# Concentrator_and_Modem_Headers.net
KiCad netlist of a schematic drawn in Altium Designer
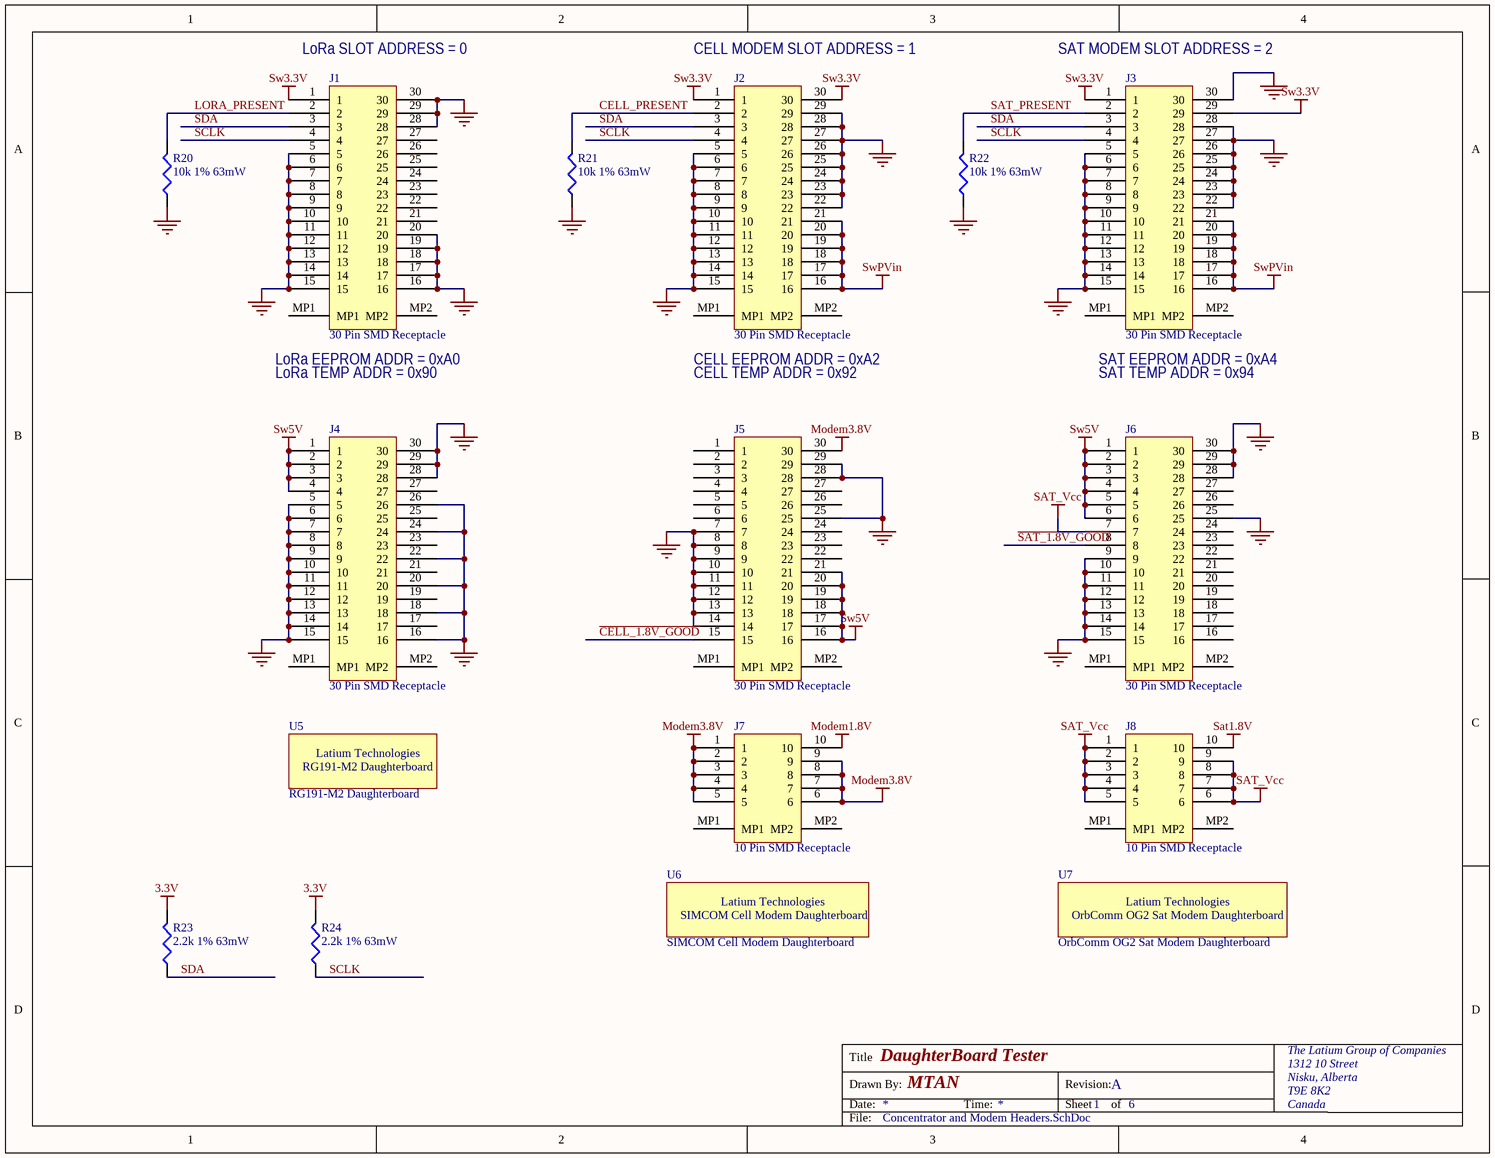
[diagram p0: Concentrator and Modem Headers.SchDoc]

(export (version "E")
  (design (tool "Eeschema 10.0.6"))
  (components
    (comp (ref "J1")
      (value "30 Pin SMD Receptacle")
      (footprint "10132798-031100LF")
      (description "CONN RCPT 30POS SMD GOLD")
      (fields
        (field (name "MANUFACTURER") "Amphenol ICC (FCI)")
        (field (name "MANUFACTURER PART NUMBER") "10132798-031100LF")
      )
      (libsource (lib "Latium Component Library") (part "Amphenol 30 Pos BergStak Plug"))
    )
    (comp (ref "J2")
      (value "30 Pin SMD Receptacle")
      (footprint "10132798-031100LF")
      (description "CONN RCPT 30POS SMD GOLD")
      (fields
        (field (name "MANUFACTURER") "Amphenol ICC (FCI)")
        (field (name "MANUFACTURER PART NUMBER") "10132798-031100LF")
      )
      (libsource (lib "Latium Component Library") (part "Amphenol 30 Pos BergStak Plug"))
    )
    (comp (ref "J3")
      (value "30 Pin SMD Receptacle")
      (footprint "10132798-031100LF")
      (description "CONN RCPT 30POS SMD GOLD")
      (fields
        (field (name "MANUFACTURER") "Amphenol ICC (FCI)")
        (field (name "MANUFACTURER PART NUMBER") "10132798-031100LF")
      )
      (libsource (lib "Latium Component Library") (part "Amphenol 30 Pos BergStak Plug"))
    )
    (comp (ref "J4")
      (value "30 Pin SMD Receptacle")
      (footprint "10132798-031100LF")
      (description "CONN RCPT 30POS SMD GOLD")
      (fields
        (field (name "MANUFACTURER") "Amphenol ICC (FCI)")
        (field (name "MANUFACTURER PART NUMBER") "10132798-031100LF")
      )
      (libsource (lib "Latium Component Library") (part "Amphenol 30 Pos BergStak Plug"))
    )
    (comp (ref "J5")
      (value "30 Pin SMD Receptacle")
      (footprint "10132798-031100LF")
      (description "CONN RCPT 30POS SMD GOLD")
      (fields
        (field (name "MANUFACTURER") "Amphenol ICC (FCI)")
        (field (name "MANUFACTURER PART NUMBER") "10132798-031100LF")
      )
      (libsource (lib "Latium Component Library") (part "Amphenol 30 Pos BergStak Plug"))
    )
    (comp (ref "J6")
      (value "30 Pin SMD Receptacle")
      (footprint "10132798-031100LF")
      (description "CONN RCPT 30POS SMD GOLD")
      (fields
        (field (name "MANUFACTURER") "Amphenol ICC (FCI)")
        (field (name "MANUFACTURER PART NUMBER") "10132798-031100LF")
      )
      (libsource (lib "Latium Component Library") (part "Amphenol 30 Pos BergStak Plug"))
    )
    (comp (ref "J7")
      (value "10 Pin SMD Receptacle")
      (footprint "10132798-011100LF")
      (description "CONN RCPT 10POS SMD GOLD")
      (fields
        (field (name "MANUFACTURER") "Amphenol ICC (FCI)")
        (field (name "MANUFACTURER PART NUMBER") "10132798-011100LF")
      )
      (libsource (lib "Latium Component Library") (part "Amphenol 10 Pos BergStak Plug"))
    )
    (comp (ref "J8")
      (value "10 Pin SMD Receptacle")
      (footprint "10132798-011100LF")
      (description "CONN RCPT 10POS SMD GOLD")
      (fields
        (field (name "MANUFACTURER") "Amphenol ICC (FCI)")
        (field (name "MANUFACTURER PART NUMBER") "10132798-011100LF")
      )
      (libsource (lib "Latium Component Library") (part "Amphenol 10 Pos BergStak Plug"))
    )
    (comp (ref "R20")
      (value "10k 1% 63mW")
      (footprint "RESC1005L")
      (description "Resistor")
      (libsource (lib "Miscellaneous Devices") (part "Res3"))
    )
    (comp (ref "R21")
      (value "10k 1% 63mW")
      (footprint "RESC1005L")
      (description "Resistor")
      (libsource (lib "Miscellaneous Devices") (part "Res3"))
    )
    (comp (ref "R22")
      (value "10k 1% 63mW")
      (footprint "RESC1005L")
      (description "Resistor")
      (libsource (lib "Miscellaneous Devices") (part "Res3"))
    )
    (comp (ref "R23")
      (value "2.2k 1% 63mW")
      (footprint "RESC1005L")
      (description "Resistor")
      (libsource (lib "Miscellaneous Devices") (part "Res3"))
    )
    (comp (ref "R24")
      (value "2.2k 1% 63mW")
      (footprint "RESC1005L")
      (description "Resistor")
      (libsource (lib "Miscellaneous Devices") (part "Res3"))
    )
    (comp (ref "U5")
      (value "RG191-M2 Daughterboard")
      (footprint "RG191-M2 LoRa Daughterboard")
      (libsource (lib "Latium Component Library") (part "RG191-M2 Daughterboard"))
    )
    (comp (ref "U6")
      (value "SIMCOM Cell Modem Daughterboard")
      (footprint "SIMCOM Cell Modem Daughterboard")
      (libsource (lib "Latium Component Library") (part "SIMCOM Cell Modem Daughterboard"))
    )
    (comp (ref "U7")
      (value "OrbComm OG2 Sat Modem Daughterboard")
      (footprint "OrbComm OG2 Daughterboard")
      (libsource (lib "Latium Component Library") (part "OrbComm OG2 Sat Modem Daughterboard"))
    )
  )
  (nets
    (net (code "1") (name "/CELL_PRESENT") (class "Default")
      (node (ref "J2") (pin "2") (pinfunction "2_2") (pintype "passive"))
      (node (ref "R21") (pin "2") (pinfunction "2_2") (pintype "passive"))
    )
    (net (code "2") (name "/LORA_PRESENT") (class "Default")
      (node (ref "J1") (pin "2") (pinfunction "2_2") (pintype "passive"))
      (node (ref "R20") (pin "2") (pinfunction "2_2") (pintype "passive"))
    )
    (net (code "3") (name "/SAT_PRESENT") (class "Default")
      (node (ref "J3") (pin "2") (pinfunction "2_2") (pintype "passive"))
      (node (ref "R22") (pin "2") (pinfunction "2_2") (pintype "passive"))
    )
    (net (code "4") (name "/SCLK") (class "Default")
      (node (ref "J1") (pin "4") (pinfunction "4_4") (pintype "passive"))
      (node (ref "J2") (pin "4") (pinfunction "4_4") (pintype "passive"))
      (node (ref "J3") (pin "4") (pinfunction "4_4") (pintype "passive"))
      (node (ref "R24") (pin "1") (pinfunction "1_1") (pintype "passive"))
    )
    (net (code "5") (name "/SDA") (class "Default")
      (node (ref "J1") (pin "3") (pinfunction "3_3") (pintype "passive"))
      (node (ref "J2") (pin "3") (pinfunction "3_3") (pintype "passive"))
      (node (ref "J3") (pin "3") (pinfunction "3_3") (pintype "passive"))
      (node (ref "R23") (pin "1") (pinfunction "1_1") (pintype "passive"))
    )
    (net (code "6") (name "/~{CELL_1.8V_GOOD}") (class "Default")
      (node (ref "J5") (pin "15") (pinfunction "15_15") (pintype "passive"))
    )
    (net (code "7") (name "/~{SAT_1.8V_GOOD}") (class "Default")
      (node (ref "J6") (pin "8") (pinfunction "8_8") (pintype "passive"))
    )
    (net (code "8") (name "3.3V") (class "Default")
      (node (ref "R23") (pin "2") (pinfunction "2_2") (pintype "passive"))
      (node (ref "R24") (pin "2") (pinfunction "2_2") (pintype "passive"))
    )
    (net (code "9") (name "GND") (class "Default")
      (node (ref "J1") (pin "10") (pinfunction "10_10") (pintype "passive"))
      (node (ref "J1") (pin "11") (pinfunction "11_11") (pintype "passive"))
      (node (ref "J1") (pin "12") (pinfunction "12_12") (pintype "passive"))
      (node (ref "J1") (pin "13") (pinfunction "13_13") (pintype "passive"))
      (node (ref "J1") (pin "14") (pinfunction "14_14") (pintype "passive"))
      (node (ref "J1") (pin "15") (pinfunction "15_15") (pintype "passive"))
      (node (ref "J1") (pin "16") (pinfunction "16_16") (pintype "passive"))
      (node (ref "J1") (pin "17") (pinfunction "17_17") (pintype "passive"))
      (node (ref "J1") (pin "18") (pinfunction "18_18") (pintype "passive"))
      (node (ref "J1") (pin "19") (pinfunction "19_19") (pintype "passive"))
      (node (ref "J1") (pin "20") (pinfunction "20_20") (pintype "passive"))
      (node (ref "J1") (pin "28") (pinfunction "28_28") (pintype "passive"))
      (node (ref "J1") (pin "29") (pinfunction "29_29") (pintype "passive"))
      (node (ref "J1") (pin "30") (pinfunction "30_30") (pintype "passive"))
      (node (ref "J1") (pin "5") (pinfunction "5_5") (pintype "passive"))
      (node (ref "J1") (pin "6") (pinfunction "6_6") (pintype "passive"))
      (node (ref "J1") (pin "7") (pinfunction "7_7") (pintype "passive"))
      (node (ref "J1") (pin "8") (pinfunction "8_8") (pintype "passive"))
      (node (ref "J1") (pin "9") (pinfunction "9_9") (pintype "passive"))
      (node (ref "J2") (pin "10") (pinfunction "10_10") (pintype "passive"))
      (node (ref "J2") (pin "11") (pinfunction "11_11") (pintype "passive"))
      (node (ref "J2") (pin "12") (pinfunction "12_12") (pintype "passive"))
      (node (ref "J2") (pin "13") (pinfunction "13_13") (pintype "passive"))
      (node (ref "J2") (pin "14") (pinfunction "14_14") (pintype "passive"))
      (node (ref "J2") (pin "15") (pinfunction "15_15") (pintype "passive"))
      (node (ref "J2") (pin "22") (pinfunction "22_22") (pintype "passive"))
      (node (ref "J2") (pin "23") (pinfunction "23_23") (pintype "passive"))
      (node (ref "J2") (pin "24") (pinfunction "24_24") (pintype "passive"))
      (node (ref "J2") (pin "25") (pinfunction "25_25") (pintype "passive"))
      (node (ref "J2") (pin "26") (pinfunction "26_26") (pintype "passive"))
      (node (ref "J2") (pin "27") (pinfunction "27_27") (pintype "passive"))
      (node (ref "J2") (pin "28") (pinfunction "28_28") (pintype "passive"))
      (node (ref "J2") (pin "29") (pinfunction "29_29") (pintype "passive"))
      (node (ref "J2") (pin "5") (pinfunction "5_5") (pintype "passive"))
      (node (ref "J2") (pin "6") (pinfunction "6_6") (pintype "passive"))
      (node (ref "J2") (pin "7") (pinfunction "7_7") (pintype "passive"))
      (node (ref "J2") (pin "8") (pinfunction "8_8") (pintype "passive"))
      (node (ref "J2") (pin "9") (pinfunction "9_9") (pintype "passive"))
      (node (ref "J3") (pin "10") (pinfunction "10_10") (pintype "passive"))
      (node (ref "J3") (pin "11") (pinfunction "11_11") (pintype "passive"))
      (node (ref "J3") (pin "12") (pinfunction "12_12") (pintype "passive"))
      (node (ref "J3") (pin "13") (pinfunction "13_13") (pintype "passive"))
      (node (ref "J3") (pin "14") (pinfunction "14_14") (pintype "passive"))
      (node (ref "J3") (pin "15") (pinfunction "15_15") (pintype "passive"))
      (node (ref "J3") (pin "22") (pinfunction "22_22") (pintype "passive"))
      (node (ref "J3") (pin "23") (pinfunction "23_23") (pintype "passive"))
      (node (ref "J3") (pin "24") (pinfunction "24_24") (pintype "passive"))
      (node (ref "J3") (pin "25") (pinfunction "25_25") (pintype "passive"))
      (node (ref "J3") (pin "26") (pinfunction "26_26") (pintype "passive"))
      (node (ref "J3") (pin "27") (pinfunction "27_27") (pintype "passive"))
      (node (ref "J3") (pin "28") (pinfunction "28_28") (pintype "passive"))
      (node (ref "J3") (pin "30") (pinfunction "30_30") (pintype "passive"))
      (node (ref "J3") (pin "5") (pinfunction "5_5") (pintype "passive"))
      (node (ref "J3") (pin "6") (pinfunction "6_6") (pintype "passive"))
      (node (ref "J3") (pin "7") (pinfunction "7_7") (pintype "passive"))
      (node (ref "J3") (pin "8") (pinfunction "8_8") (pintype "passive"))
      (node (ref "J3") (pin "9") (pinfunction "9_9") (pintype "passive"))
      (node (ref "J4") (pin "10") (pinfunction "10_10") (pintype "passive"))
      (node (ref "J4") (pin "11") (pinfunction "11_11") (pintype "passive"))
      (node (ref "J4") (pin "12") (pinfunction "12_12") (pintype "passive"))
      (node (ref "J4") (pin "13") (pinfunction "13_13") (pintype "passive"))
      (node (ref "J4") (pin "14") (pinfunction "14_14") (pintype "passive"))
      (node (ref "J4") (pin "15") (pinfunction "15_15") (pintype "passive"))
      (node (ref "J4") (pin "16") (pinfunction "16_16") (pintype "passive"))
      (node (ref "J4") (pin "18") (pinfunction "18_18") (pintype "passive"))
      (node (ref "J4") (pin "20") (pinfunction "20_20") (pintype "passive"))
      (node (ref "J4") (pin "22") (pinfunction "22_22") (pintype "passive"))
      (node (ref "J4") (pin "24") (pinfunction "24_24") (pintype "passive"))
      (node (ref "J4") (pin "26") (pinfunction "26_26") (pintype "passive"))
      (node (ref "J4") (pin "28") (pinfunction "28_28") (pintype "passive"))
      (node (ref "J4") (pin "29") (pinfunction "29_29") (pintype "passive"))
      (node (ref "J4") (pin "30") (pinfunction "30_30") (pintype "passive"))
      (node (ref "J4") (pin "5") (pinfunction "5_5") (pintype "passive"))
      (node (ref "J4") (pin "6") (pinfunction "6_6") (pintype "passive"))
      (node (ref "J4") (pin "7") (pinfunction "7_7") (pintype "passive"))
      (node (ref "J4") (pin "8") (pinfunction "8_8") (pintype "passive"))
      (node (ref "J4") (pin "9") (pinfunction "9_9") (pintype "passive"))
      (node (ref "J5") (pin "10") (pinfunction "10_10") (pintype "passive"))
      (node (ref "J5") (pin "11") (pinfunction "11_11") (pintype "passive"))
      (node (ref "J5") (pin "12") (pinfunction "12_12") (pintype "passive"))
      (node (ref "J5") (pin "13") (pinfunction "13_13") (pintype "passive"))
      (node (ref "J5") (pin "14") (pinfunction "14_14") (pintype "passive"))
      (node (ref "J5") (pin "25") (pinfunction "25_25") (pintype "passive"))
      (node (ref "J5") (pin "28") (pinfunction "28_28") (pintype "passive"))
      (node (ref "J5") (pin "29") (pinfunction "29_29") (pintype "passive"))
      (node (ref "J5") (pin "7") (pinfunction "7_7") (pintype "passive"))
      (node (ref "J5") (pin "8") (pinfunction "8_8") (pintype "passive"))
      (node (ref "J5") (pin "9") (pinfunction "9_9") (pintype "passive"))
      (node (ref "J6") (pin "10") (pinfunction "10_10") (pintype "passive"))
      (node (ref "J6") (pin "11") (pinfunction "11_11") (pintype "passive"))
      (node (ref "J6") (pin "12") (pinfunction "12_12") (pintype "passive"))
      (node (ref "J6") (pin "13") (pinfunction "13_13") (pintype "passive"))
      (node (ref "J6") (pin "14") (pinfunction "14_14") (pintype "passive"))
      (node (ref "J6") (pin "15") (pinfunction "15_15") (pintype "passive"))
      (node (ref "J6") (pin "25") (pinfunction "25_25") (pintype "passive"))
      (node (ref "J6") (pin "28") (pinfunction "28_28") (pintype "passive"))
      (node (ref "J6") (pin "29") (pinfunction "29_29") (pintype "passive"))
      (node (ref "J6") (pin "30") (pinfunction "30_30") (pintype "passive"))
      (node (ref "J6") (pin "9") (pinfunction "9_9") (pintype "passive"))
      (node (ref "R20") (pin "1") (pinfunction "1_1") (pintype "passive"))
      (node (ref "R21") (pin "1") (pinfunction "1_1") (pintype "passive"))
      (node (ref "R22") (pin "1") (pinfunction "1_1") (pintype "passive"))
    )
    (net (code "10") (name "Modem1.8V") (class "Default")
      (node (ref "J7") (pin "10") (pinfunction "10_10") (pintype "passive"))
    )
    (net (code "11") (name "Modem3.8V") (class "Default")
      (node (ref "J5") (pin "30") (pinfunction "30_30") (pintype "passive"))
      (node (ref "J7") (pin "1") (pinfunction "1_1") (pintype "passive"))
      (node (ref "J7") (pin "2") (pinfunction "2_2") (pintype "passive"))
      (node (ref "J7") (pin "3") (pinfunction "3_3") (pintype "passive"))
      (node (ref "J7") (pin "4") (pinfunction "4_4") (pintype "passive"))
      (node (ref "J7") (pin "5") (pinfunction "5_5") (pintype "passive"))
      (node (ref "J7") (pin "6") (pinfunction "6_6") (pintype "passive"))
      (node (ref "J7") (pin "7") (pinfunction "7_7") (pintype "passive"))
      (node (ref "J7") (pin "8") (pinfunction "8_8") (pintype "passive"))
      (node (ref "J7") (pin "9") (pinfunction "9_9") (pintype "passive"))
    )
    (net (code "12") (name "SAT_Vcc") (class "Default")
      (node (ref "J6") (pin "7") (pinfunction "7_7") (pintype "passive"))
      (node (ref "J8") (pin "1") (pinfunction "1_1") (pintype "passive"))
      (node (ref "J8") (pin "2") (pinfunction "2_2") (pintype "passive"))
      (node (ref "J8") (pin "3") (pinfunction "3_3") (pintype "passive"))
      (node (ref "J8") (pin "4") (pinfunction "4_4") (pintype "passive"))
      (node (ref "J8") (pin "5") (pinfunction "5_5") (pintype "passive"))
      (node (ref "J8") (pin "6") (pinfunction "6_6") (pintype "passive"))
      (node (ref "J8") (pin "7") (pinfunction "7_7") (pintype "passive"))
      (node (ref "J8") (pin "8") (pinfunction "8_8") (pintype "passive"))
      (node (ref "J8") (pin "9") (pinfunction "9_9") (pintype "passive"))
    )
    (net (code "13") (name "Sat1.8V") (class "Default")
      (node (ref "J8") (pin "10") (pinfunction "10_10") (pintype "passive"))
    )
    (net (code "14") (name "Sw3.3V") (class "Default")
      (node (ref "J1") (pin "1") (pinfunction "1_1") (pintype "passive"))
      (node (ref "J2") (pin "1") (pinfunction "1_1") (pintype "passive"))
      (node (ref "J2") (pin "30") (pinfunction "30_30") (pintype "passive"))
      (node (ref "J3") (pin "1") (pinfunction "1_1") (pintype "passive"))
      (node (ref "J3") (pin "29") (pinfunction "29_29") (pintype "passive"))
    )
    (net (code "15") (name "Sw5V") (class "Default")
      (node (ref "J4") (pin "1") (pinfunction "1_1") (pintype "passive"))
      (node (ref "J4") (pin "2") (pinfunction "2_2") (pintype "passive"))
      (node (ref "J4") (pin "3") (pinfunction "3_3") (pintype "passive"))
      (node (ref "J4") (pin "4") (pinfunction "4_4") (pintype "passive"))
      (node (ref "J5") (pin "16") (pinfunction "16_16") (pintype "passive"))
      (node (ref "J5") (pin "17") (pinfunction "17_17") (pintype "passive"))
      (node (ref "J5") (pin "18") (pinfunction "18_18") (pintype "passive"))
      (node (ref "J5") (pin "19") (pinfunction "19_19") (pintype "passive"))
      (node (ref "J5") (pin "20") (pinfunction "20_20") (pintype "passive"))
      (node (ref "J5") (pin "21") (pinfunction "21_21") (pintype "passive"))
      (node (ref "J6") (pin "1") (pinfunction "1_1") (pintype "passive"))
      (node (ref "J6") (pin "2") (pinfunction "2_2") (pintype "passive"))
      (node (ref "J6") (pin "3") (pinfunction "3_3") (pintype "passive"))
      (node (ref "J6") (pin "4") (pinfunction "4_4") (pintype "passive"))
      (node (ref "J6") (pin "5") (pinfunction "5_5") (pintype "passive"))
      (node (ref "J6") (pin "6") (pinfunction "6_6") (pintype "passive"))
    )
    (net (code "16") (name "SwPVin") (class "Default")
      (node (ref "J2") (pin "16") (pinfunction "16_16") (pintype "passive"))
      (node (ref "J2") (pin "17") (pinfunction "17_17") (pintype "passive"))
      (node (ref "J2") (pin "18") (pinfunction "18_18") (pintype "passive"))
      (node (ref "J2") (pin "19") (pinfunction "19_19") (pintype "passive"))
      (node (ref "J2") (pin "20") (pinfunction "20_20") (pintype "passive"))
      (node (ref "J2") (pin "21") (pinfunction "21_21") (pintype "passive"))
      (node (ref "J3") (pin "16") (pinfunction "16_16") (pintype "passive"))
      (node (ref "J3") (pin "17") (pinfunction "17_17") (pintype "passive"))
      (node (ref "J3") (pin "18") (pinfunction "18_18") (pintype "passive"))
      (node (ref "J3") (pin "19") (pinfunction "19_19") (pintype "passive"))
      (node (ref "J3") (pin "20") (pinfunction "20_20") (pintype "passive"))
      (node (ref "J3") (pin "21") (pinfunction "21_21") (pintype "passive"))
    )
    (net (code "17") (name "unconnected-(J1-Pad21)") (class "Default")
      (node (ref "J1") (pin "21") (pinfunction "21_21") (pintype "passive"))
    )
    (net (code "18") (name "unconnected-(J1-Pad22)") (class "Default")
      (node (ref "J1") (pin "22") (pinfunction "22_22") (pintype "passive"))
    )
    (net (code "19") (name "unconnected-(J1-Pad23)") (class "Default")
      (node (ref "J1") (pin "23") (pinfunction "23_23") (pintype "passive"))
    )
    (net (code "20") (name "unconnected-(J1-Pad24)") (class "Default")
      (node (ref "J1") (pin "24") (pinfunction "24_24") (pintype "passive"))
    )
    (net (code "21") (name "unconnected-(J1-Pad25)") (class "Default")
      (node (ref "J1") (pin "25") (pinfunction "25_25") (pintype "passive"))
    )
    (net (code "22") (name "unconnected-(J1-Pad26)") (class "Default")
      (node (ref "J1") (pin "26") (pinfunction "26_26") (pintype "passive"))
    )
    (net (code "23") (name "unconnected-(J1-Pad27)") (class "Default")
      (node (ref "J1") (pin "27") (pinfunction "27_27") (pintype "passive"))
    )
    (net (code "24") (name "unconnected-(J1-PadMP1)") (class "Default")
      (node (ref "J1") (pin "MP1") (pinfunction "MP1_MP1") (pintype "passive"))
    )
    (net (code "25") (name "unconnected-(J1-PadMP2)") (class "Default")
      (node (ref "J1") (pin "MP2") (pinfunction "MP2_MP2") (pintype "passive"))
    )
    (net (code "26") (name "unconnected-(J2-PadMP1)") (class "Default")
      (node (ref "J2") (pin "MP1") (pinfunction "MP1_MP1") (pintype "passive"))
    )
    (net (code "27") (name "unconnected-(J2-PadMP2)") (class "Default")
      (node (ref "J2") (pin "MP2") (pinfunction "MP2_MP2") (pintype "passive"))
    )
    (net (code "28") (name "unconnected-(J3-PadMP1)") (class "Default")
      (node (ref "J3") (pin "MP1") (pinfunction "MP1_MP1") (pintype "passive"))
    )
    (net (code "29") (name "unconnected-(J3-PadMP2)") (class "Default")
      (node (ref "J3") (pin "MP2") (pinfunction "MP2_MP2") (pintype "passive"))
    )
    (net (code "30") (name "unconnected-(J4-Pad17)") (class "Default")
      (node (ref "J4") (pin "17") (pinfunction "17_17") (pintype "passive"))
    )
    (net (code "31") (name "unconnected-(J4-Pad19)") (class "Default")
      (node (ref "J4") (pin "19") (pinfunction "19_19") (pintype "passive"))
    )
    (net (code "32") (name "unconnected-(J4-Pad21)") (class "Default")
      (node (ref "J4") (pin "21") (pinfunction "21_21") (pintype "passive"))
    )
    (net (code "33") (name "unconnected-(J4-Pad23)") (class "Default")
      (node (ref "J4") (pin "23") (pinfunction "23_23") (pintype "passive"))
    )
    (net (code "34") (name "unconnected-(J4-Pad25)") (class "Default")
      (node (ref "J4") (pin "25") (pinfunction "25_25") (pintype "passive"))
    )
    (net (code "35") (name "unconnected-(J4-Pad27)") (class "Default")
      (node (ref "J4") (pin "27") (pinfunction "27_27") (pintype "passive"))
    )
    (net (code "36") (name "unconnected-(J4-PadMP1)") (class "Default")
      (node (ref "J4") (pin "MP1") (pinfunction "MP1_MP1") (pintype "passive"))
    )
    (net (code "37") (name "unconnected-(J4-PadMP2)") (class "Default")
      (node (ref "J4") (pin "MP2") (pinfunction "MP2_MP2") (pintype "passive"))
    )
    (net (code "38") (name "unconnected-(J5-Pad1)") (class "Default")
      (node (ref "J5") (pin "1") (pinfunction "1_1") (pintype "passive"))
    )
    (net (code "39") (name "unconnected-(J5-Pad2)") (class "Default")
      (node (ref "J5") (pin "2") (pinfunction "2_2") (pintype "passive"))
    )
    (net (code "40") (name "unconnected-(J5-Pad3)") (class "Default")
      (node (ref "J5") (pin "3") (pinfunction "3_3") (pintype "passive"))
    )
    (net (code "41") (name "unconnected-(J5-Pad4)") (class "Default")
      (node (ref "J5") (pin "4") (pinfunction "4_4") (pintype "passive"))
    )
    (net (code "42") (name "unconnected-(J5-Pad5)") (class "Default")
      (node (ref "J5") (pin "5") (pinfunction "5_5") (pintype "passive"))
    )
    (net (code "43") (name "unconnected-(J5-Pad6)") (class "Default")
      (node (ref "J5") (pin "6") (pinfunction "6_6") (pintype "passive"))
    )
    (net (code "44") (name "unconnected-(J5-Pad22)") (class "Default")
      (node (ref "J5") (pin "22") (pinfunction "22_22") (pintype "passive"))
    )
    (net (code "45") (name "unconnected-(J5-Pad23)") (class "Default")
      (node (ref "J5") (pin "23") (pinfunction "23_23") (pintype "passive"))
    )
    (net (code "46") (name "unconnected-(J5-Pad24)") (class "Default")
      (node (ref "J5") (pin "24") (pinfunction "24_24") (pintype "passive"))
    )
    (net (code "47") (name "unconnected-(J5-Pad26)") (class "Default")
      (node (ref "J5") (pin "26") (pinfunction "26_26") (pintype "passive"))
    )
    (net (code "48") (name "unconnected-(J5-Pad27)") (class "Default")
      (node (ref "J5") (pin "27") (pinfunction "27_27") (pintype "passive"))
    )
    (net (code "49") (name "unconnected-(J5-PadMP1)") (class "Default")
      (node (ref "J5") (pin "MP1") (pinfunction "MP1_MP1") (pintype "passive"))
    )
    (net (code "50") (name "unconnected-(J5-PadMP2)") (class "Default")
      (node (ref "J5") (pin "MP2") (pinfunction "MP2_MP2") (pintype "passive"))
    )
    (net (code "51") (name "unconnected-(J6-Pad16)") (class "Default")
      (node (ref "J6") (pin "16") (pinfunction "16_16") (pintype "passive"))
    )
    (net (code "52") (name "unconnected-(J6-Pad17)") (class "Default")
      (node (ref "J6") (pin "17") (pinfunction "17_17") (pintype "passive"))
    )
    (net (code "53") (name "unconnected-(J6-Pad18)") (class "Default")
      (node (ref "J6") (pin "18") (pinfunction "18_18") (pintype "passive"))
    )
    (net (code "54") (name "unconnected-(J6-Pad19)") (class "Default")
      (node (ref "J6") (pin "19") (pinfunction "19_19") (pintype "passive"))
    )
    (net (code "55") (name "unconnected-(J6-Pad20)") (class "Default")
      (node (ref "J6") (pin "20") (pinfunction "20_20") (pintype "passive"))
    )
    (net (code "56") (name "unconnected-(J6-Pad21)") (class "Default")
      (node (ref "J6") (pin "21") (pinfunction "21_21") (pintype "passive"))
    )
    (net (code "57") (name "unconnected-(J6-Pad22)") (class "Default")
      (node (ref "J6") (pin "22") (pinfunction "22_22") (pintype "passive"))
    )
    (net (code "58") (name "unconnected-(J6-Pad23)") (class "Default")
      (node (ref "J6") (pin "23") (pinfunction "23_23") (pintype "passive"))
    )
    (net (code "59") (name "unconnected-(J6-Pad24)") (class "Default")
      (node (ref "J6") (pin "24") (pinfunction "24_24") (pintype "passive"))
    )
    (net (code "60") (name "unconnected-(J6-Pad26)") (class "Default")
      (node (ref "J6") (pin "26") (pinfunction "26_26") (pintype "passive"))
    )
    (net (code "61") (name "unconnected-(J6-Pad27)") (class "Default")
      (node (ref "J6") (pin "27") (pinfunction "27_27") (pintype "passive"))
    )
    (net (code "62") (name "unconnected-(J6-PadMP1)") (class "Default")
      (node (ref "J6") (pin "MP1") (pinfunction "MP1_MP1") (pintype "passive"))
    )
    (net (code "63") (name "unconnected-(J6-PadMP2)") (class "Default")
      (node (ref "J6") (pin "MP2") (pinfunction "MP2_MP2") (pintype "passive"))
    )
    (net (code "64") (name "unconnected-(J7-PadMP1)") (class "Default")
      (node (ref "J7") (pin "MP1") (pinfunction "MP1_MP1") (pintype "passive"))
    )
    (net (code "65") (name "unconnected-(J7-PadMP2)") (class "Default")
      (node (ref "J7") (pin "MP2") (pinfunction "MP2_MP2") (pintype "passive"))
    )
    (net (code "66") (name "unconnected-(J8-PadMP1)") (class "Default")
      (node (ref "J8") (pin "MP1") (pinfunction "MP1_MP1") (pintype "passive"))
    )
    (net (code "67") (name "unconnected-(J8-PadMP2)") (class "Default")
      (node (ref "J8") (pin "MP2") (pinfunction "MP2_MP2") (pintype "passive"))
    )
  )
)
